# transistor_schematic.net
KiCad netlist of a schematic drawn in EAGLE
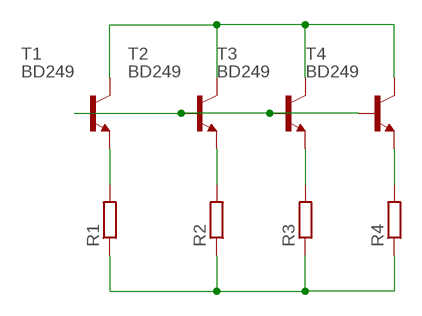
[diagram p0: schematic, sheet 1]

(export (version "E")
  (design (tool "Eeschema 10.0.6"))
  (components
    (comp (ref "R1")
      (value "R-EU_VTA53")
      (footprint "eagle-import:VTA53")
      (libsource (lib "eagle-import") (part "R-EU_VTA53"))
    )
    (comp (ref "R2")
      (value "R-EU_VTA53")
      (footprint "eagle-import:VTA53")
      (libsource (lib "eagle-import") (part "R-EU_VTA53"))
    )
    (comp (ref "R3")
      (value "R-EU_VTA53")
      (footprint "eagle-import:VTA53")
      (libsource (lib "eagle-import") (part "R-EU_VTA53"))
    )
    (comp (ref "R4")
      (value "R-EU_VTA53")
      (footprint "eagle-import:VTA53")
      (libsource (lib "eagle-import") (part "R-EU_VTA53"))
    )
    (comp (ref "T1")
      (value "BD249")
      (footprint "eagle-import:TOP3")
      (libsource (lib "eagle-import") (part "BD249"))
    )
    (comp (ref "T2")
      (value "BD249")
      (footprint "eagle-import:TOP3")
      (libsource (lib "eagle-import") (part "BD249"))
    )
    (comp (ref "T3")
      (value "BD249")
      (footprint "eagle-import:TOP3")
      (libsource (lib "eagle-import") (part "BD249"))
    )
    (comp (ref "T4")
      (value "BD249")
      (footprint "eagle-import:TOP3")
      (libsource (lib "eagle-import") (part "BD249"))
    )
  )
  (nets
    (net (code "1") (name "Net-(R1-Pad1)") (class "Default")
      (node (ref "R1") (pin "1") (pinfunction "1_1") (pintype "passive"))
      (node (ref "R2") (pin "1") (pinfunction "1_1") (pintype "passive"))
      (node (ref "R3") (pin "1") (pinfunction "1_1") (pintype "passive"))
      (node (ref "R4") (pin "1") (pinfunction "1_1") (pintype "passive"))
    )
    (net (code "2") (name "Net-(T1-B)") (class "Default")
      (node (ref "T1") (pin "1") (pinfunction "B_1") (pintype "passive"))
      (node (ref "T2") (pin "1") (pinfunction "B_1") (pintype "passive"))
      (node (ref "T3") (pin "1") (pinfunction "B_1") (pintype "passive"))
      (node (ref "T4") (pin "1") (pinfunction "B_1") (pintype "passive"))
    )
    (net (code "3") (name "Net-(T1-C)") (class "Default")
      (node (ref "T1") (pin "2") (pinfunction "C_2") (pintype "passive"))
      (node (ref "T2") (pin "2") (pinfunction "C_2") (pintype "passive"))
      (node (ref "T3") (pin "2") (pinfunction "C_2") (pintype "passive"))
      (node (ref "T4") (pin "2") (pinfunction "C_2") (pintype "passive"))
    )
    (net (code "4") (name "Net-(T1-E)") (class "Default")
      (node (ref "R1") (pin "2") (pinfunction "2_2") (pintype "passive"))
      (node (ref "T1") (pin "3") (pinfunction "E_3") (pintype "passive"))
    )
    (net (code "5") (name "Net-(T2-E)") (class "Default")
      (node (ref "R2") (pin "2") (pinfunction "2_2") (pintype "passive"))
      (node (ref "T2") (pin "3") (pinfunction "E_3") (pintype "passive"))
    )
    (net (code "6") (name "Net-(T3-E)") (class "Default")
      (node (ref "R3") (pin "2") (pinfunction "2_2") (pintype "passive"))
      (node (ref "T3") (pin "3") (pinfunction "E_3") (pintype "passive"))
    )
    (net (code "7") (name "Net-(T4-E)") (class "Default")
      (node (ref "R4") (pin "2") (pinfunction "2_2") (pintype "passive"))
      (node (ref "T4") (pin "3") (pinfunction "E_3") (pintype "passive"))
    )
  )
)
